# STM32RF_BME280.net
KiCad netlist of a schematic drawn in Altium Designer
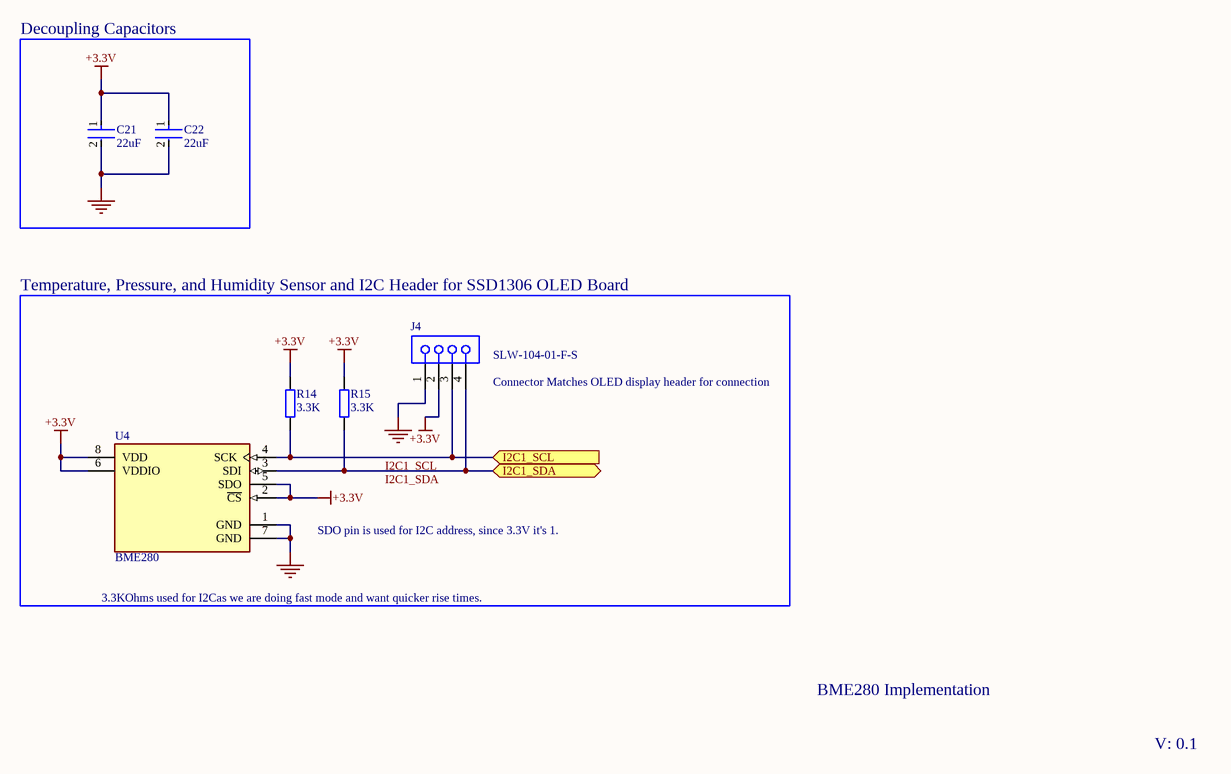
[diagram p0: STM32RF_BME280.SchDoc]

(export (version "E")
  (design (tool "Eeschema 10.0.6"))
  (components
    (comp (ref "C21")
      (value "22uF")
      (footprint "FP-GRM158-0_2-MFG")
      (description "Chip Multilayer Ceramic Capacitors for General Purpose, 0402, 22uF, X5R, 15%, 20%, 10V")
      (libsource (lib "Altium Content Vault") (part "b4654b650e69147ec39a6b967a45e02"))
    )
    (comp (ref "C22")
      (value "22uF")
      (footprint "FP-GRM158-0_2-MFG")
      (description "Chip Multilayer Ceramic Capacitors for General Purpose, 0402, 22uF, X5R, 15%, 20%, 10V")
      (libsource (lib "Altium Content Vault") (part "b4654b650e69147ec39a6b967a45e02"))
    )
    (comp (ref "J4")
      (value "SLW-104-01-F-S")
      (footprint "SMTC-SLW-104-01-X-S")
      (fields (field (name "MANUFACTURER") "Samtec"))
      (libsource (lib "Altium Content Vault") (part "SMTC-SLW-104-01-X-S"))
    )
    (comp (ref "R14")
      (value "3.3K")
      (footprint "RES_0402")
      (description "Resistor SMD 0402")
      (libsource (lib "Schematic-Lib-PhilsLab") (part "RES_0402"))
    )
    (comp (ref "R15")
      (value "3.3K")
      (footprint "RES_0402")
      (description "Resistor SMD 0402")
      (libsource (lib "Schematic-Lib-PhilsLab") (part "RES_0402"))
    )
    (comp (ref "U4")
      (value "BME280")
      (footprint "FP-BME280-MFG")
      (description "SENSOR PRESSURE HUMIDITY TEMP")
      (libsource (lib "Altium Content Vault") (part "d58e2f6669bc67e6a2bc6a28610ca79"))
    )
  )
  (nets
    (net (code "1") (name "+3.3V") (class "Default")
      (node (ref "C21") (pin "1") (pinfunction "1_1") (pintype "passive"))
      (node (ref "C22") (pin "1") (pinfunction "1_1") (pintype "passive"))
      (node (ref "J4") (pin "2") (pinfunction "2_2") (pintype "passive"))
      (node (ref "R14") (pin "2") (pinfunction "2_2") (pintype "passive"))
      (node (ref "R15") (pin "2") (pinfunction "2_2") (pintype "passive"))
      (node (ref "U4") (pin "2") (pinfunction "~{CS}_2") (pintype "input"))
      (node (ref "U4") (pin "5") (pinfunction "SDO_5") (pintype "passive"))
      (node (ref "U4") (pin "6") (pinfunction "VDDIO_6") (pintype "power_in"))
      (node (ref "U4") (pin "8") (pinfunction "VDD_8") (pintype "power_in"))
    )
    (net (code "2") (name "/I2C1_SCL") (class "Default")
      (node (ref "J4") (pin "3") (pinfunction "3_3") (pintype "passive"))
      (node (ref "R14") (pin "1") (pinfunction "1_1") (pintype "passive"))
      (node (ref "U4") (pin "4") (pinfunction "SCK_4") (pintype "input"))
    )
    (net (code "3") (name "/I2C1_SDA") (class "Default")
      (node (ref "J4") (pin "4") (pinfunction "4_4") (pintype "passive"))
      (node (ref "R15") (pin "1") (pinfunction "1_1") (pintype "passive"))
      (node (ref "U4") (pin "3") (pinfunction "SDI_3") (pintype "bidirectional"))
    )
    (net (code "4") (name "GND") (class "Default")
      (node (ref "C21") (pin "2") (pinfunction "2_2") (pintype "passive"))
      (node (ref "C22") (pin "2") (pinfunction "2_2") (pintype "passive"))
      (node (ref "J4") (pin "1") (pinfunction "1_1") (pintype "passive"))
      (node (ref "U4") (pin "1") (pinfunction "GND_1") (pintype "power_in"))
      (node (ref "U4") (pin "7") (pinfunction "GND_7") (pintype "power_in"))
    )
  )
)
